# VGA.net
KiCad netlist of a schematic drawn in Altium Designer
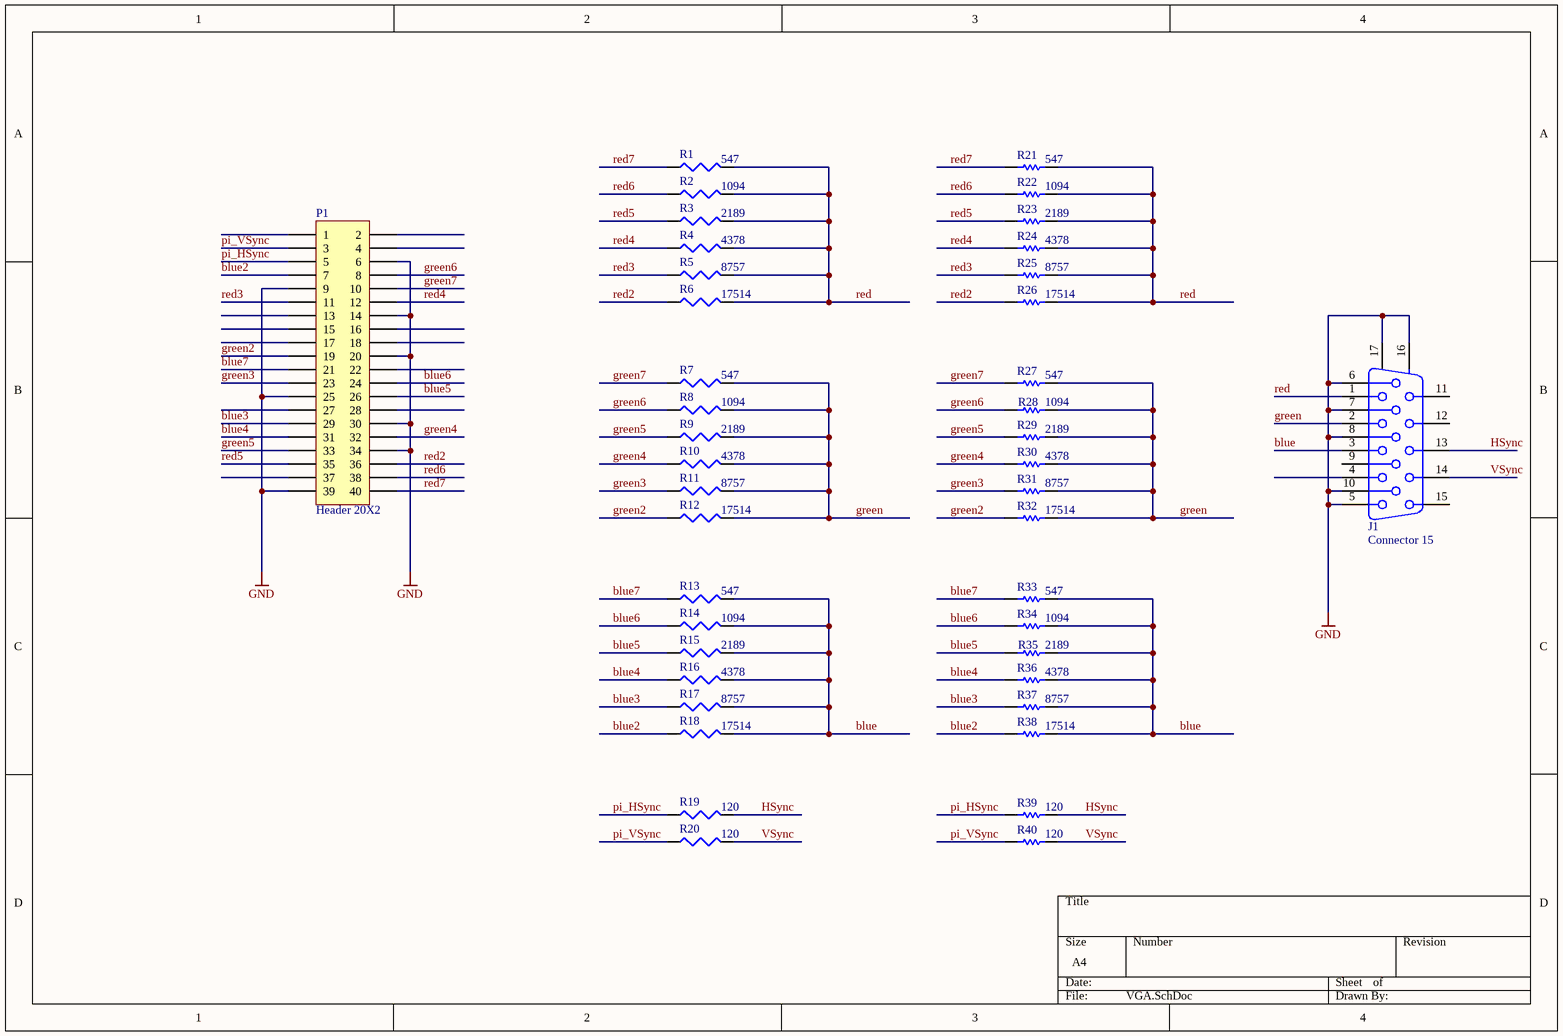
[diagram p0: VGA.SchDoc]

(export (version "E")
  (design (tool "Eeschema 10.0.6"))
  (components
    (comp (ref "J1")
      (value "Connector 15")
      (footprint "MOLEX_048203-6043")
      (description "Receptacle Assembly, 15-Pin, Sim Line Connector")
      (fields (field (name "PUBLISHER") "Altium Limited"))
      (libsource (lib "Miscellaneous Connectors") (part "Connector 15"))
    )
    (comp (ref "P1")
      (value "Header 20X2")
      (footprint "HDR2X20")
      (description "Header, 20-Pin, Dual row")
      (fields (field (name "PUBLISHER") "Altium Limited"))
      (libsource (lib "Miscellaneous Connectors") (part "Header 20X2"))
    )
    (comp (ref "R1")
      (value "547")
      (footprint "J1-0603")
      (description "Resistor")
      (fields (field (name "Comment") "Res3") (field (name "PUBLISHER") "Altium Limited"))
      (libsource (lib "Miscellaneous Devices") (part "Res3"))
    )
    (comp (ref "R2")
      (value "1094")
      (footprint "J1-0603")
      (description "Resistor")
      (fields (field (name "Comment") "Res3") (field (name "PUBLISHER") "Altium Limited"))
      (libsource (lib "Miscellaneous Devices") (part "Res3"))
    )
    (comp (ref "R3")
      (value "2189")
      (footprint "J1-0603")
      (description "Resistor")
      (fields (field (name "Comment") "Res3") (field (name "PUBLISHER") "Altium Limited"))
      (libsource (lib "Miscellaneous Devices") (part "Res3"))
    )
    (comp (ref "R4")
      (value "4378")
      (footprint "J1-0603")
      (description "Resistor")
      (fields (field (name "Comment") "Res3") (field (name "PUBLISHER") "Altium Limited"))
      (libsource (lib "Miscellaneous Devices") (part "Res3"))
    )
    (comp (ref "R5")
      (value "8757")
      (footprint "J1-0603")
      (description "Resistor")
      (fields (field (name "Comment") "Res3") (field (name "PUBLISHER") "Altium Limited"))
      (libsource (lib "Miscellaneous Devices") (part "Res3"))
    )
    (comp (ref "R6")
      (value "17514")
      (footprint "J1-0603")
      (description "Resistor")
      (fields (field (name "Comment") "Res3") (field (name "PUBLISHER") "Altium Limited"))
      (libsource (lib "Miscellaneous Devices") (part "Res3"))
    )
    (comp (ref "R7")
      (value "547")
      (footprint "J1-0603")
      (description "Resistor")
      (fields (field (name "Comment") "Res3") (field (name "PUBLISHER") "Altium Limited"))
      (libsource (lib "Miscellaneous Devices") (part "Res3"))
    )
    (comp (ref "R8")
      (value "1094")
      (footprint "J1-0603")
      (description "Resistor")
      (fields (field (name "Comment") "Res3") (field (name "PUBLISHER") "Altium Limited"))
      (libsource (lib "Miscellaneous Devices") (part "Res3"))
    )
    (comp (ref "R9")
      (value "2189")
      (footprint "J1-0603")
      (description "Resistor")
      (fields (field (name "Comment") "Res3") (field (name "PUBLISHER") "Altium Limited"))
      (libsource (lib "Miscellaneous Devices") (part "Res3"))
    )
    (comp (ref "R10")
      (value "4378")
      (footprint "J1-0603")
      (description "Resistor")
      (fields (field (name "Comment") "Res3") (field (name "PUBLISHER") "Altium Limited"))
      (libsource (lib "Miscellaneous Devices") (part "Res3"))
    )
    (comp (ref "R11")
      (value "8757")
      (footprint "J1-0603")
      (description "Resistor")
      (fields (field (name "Comment") "Res3") (field (name "PUBLISHER") "Altium Limited"))
      (libsource (lib "Miscellaneous Devices") (part "Res3"))
    )
    (comp (ref "R12")
      (value "17514")
      (footprint "J1-0603")
      (description "Resistor")
      (fields (field (name "Comment") "Res3") (field (name "PUBLISHER") "Altium Limited"))
      (libsource (lib "Miscellaneous Devices") (part "Res3"))
    )
    (comp (ref "R13")
      (value "547")
      (footprint "J1-0603")
      (description "Resistor")
      (fields (field (name "Comment") "Res3") (field (name "PUBLISHER") "Altium Limited"))
      (libsource (lib "Miscellaneous Devices") (part "Res3"))
    )
    (comp (ref "R14")
      (value "1094")
      (footprint "J1-0603")
      (description "Resistor")
      (fields (field (name "Comment") "Res3") (field (name "PUBLISHER") "Altium Limited"))
      (libsource (lib "Miscellaneous Devices") (part "Res3"))
    )
    (comp (ref "R15")
      (value "2189")
      (footprint "J1-0603")
      (description "Resistor")
      (fields (field (name "Comment") "Res3") (field (name "PUBLISHER") "Altium Limited"))
      (libsource (lib "Miscellaneous Devices") (part "Res3"))
    )
    (comp (ref "R16")
      (value "4378")
      (footprint "J1-0603")
      (description "Resistor")
      (fields (field (name "Comment") "Res3") (field (name "PUBLISHER") "Altium Limited"))
      (libsource (lib "Miscellaneous Devices") (part "Res3"))
    )
    (comp (ref "R17")
      (value "8757")
      (footprint "J1-0603")
      (description "Resistor")
      (fields (field (name "Comment") "Res3") (field (name "PUBLISHER") "Altium Limited"))
      (libsource (lib "Miscellaneous Devices") (part "Res3"))
    )
    (comp (ref "R18")
      (value "17514")
      (footprint "J1-0603")
      (description "Resistor")
      (fields (field (name "Comment") "Res3") (field (name "PUBLISHER") "Altium Limited"))
      (libsource (lib "Miscellaneous Devices") (part "Res3"))
    )
    (comp (ref "R19")
      (value "120")
      (footprint "J1-0603")
      (description "Resistor")
      (fields (field (name "Comment") "Res3") (field (name "PUBLISHER") "Altium Limited"))
      (libsource (lib "Miscellaneous Devices") (part "Res3"))
    )
    (comp (ref "R20")
      (value "120")
      (footprint "J1-0603")
      (description "Resistor")
      (fields (field (name "Comment") "Res3") (field (name "PUBLISHER") "Altium Limited"))
      (libsource (lib "Miscellaneous Devices") (part "Res3"))
    )
    (comp (ref "R21")
      (value "547")
      (footprint "AXIAL-0.3")
      (description "Resistor")
      (fields (field (name "Comment") "Res1") (field (name "PUBLISHER") "Altium Limited"))
      (libsource (lib "Miscellaneous Devices") (part "Res1"))
    )
    (comp (ref "R22")
      (value "1094")
      (footprint "AXIAL-0.3")
      (description "Resistor")
      (fields (field (name "Comment") "Res1") (field (name "PUBLISHER") "Altium Limited"))
      (libsource (lib "Miscellaneous Devices") (part "Res1"))
    )
    (comp (ref "R23")
      (value "2189")
      (footprint "AXIAL-0.3")
      (description "Resistor")
      (fields (field (name "Comment") "Res1") (field (name "PUBLISHER") "Altium Limited"))
      (libsource (lib "Miscellaneous Devices") (part "Res1"))
    )
    (comp (ref "R24")
      (value "4378")
      (footprint "AXIAL-0.3")
      (description "Resistor")
      (fields (field (name "Comment") "Res1") (field (name "PUBLISHER") "Altium Limited"))
      (libsource (lib "Miscellaneous Devices") (part "Res1"))
    )
    (comp (ref "R25")
      (value "8757")
      (footprint "AXIAL-0.3")
      (description "Resistor")
      (fields (field (name "Comment") "Res1") (field (name "PUBLISHER") "Altium Limited"))
      (libsource (lib "Miscellaneous Devices") (part "Res1"))
    )
    (comp (ref "R26")
      (value "17514")
      (footprint "AXIAL-0.3")
      (description "Resistor")
      (fields (field (name "Comment") "Res1") (field (name "PUBLISHER") "Altium Limited"))
      (libsource (lib "Miscellaneous Devices") (part "Res1"))
    )
    (comp (ref "R27")
      (value "547")
      (footprint "AXIAL-0.3")
      (description "Resistor")
      (fields (field (name "Comment") "Res1") (field (name "PUBLISHER") "Altium Limited"))
      (libsource (lib "Miscellaneous Devices") (part "Res1"))
    )
    (comp (ref "R28")
      (value "1094")
      (footprint "AXIAL-0.3")
      (description "Resistor")
      (fields (field (name "Comment") "Res1") (field (name "PUBLISHER") "Altium Limited"))
      (libsource (lib "Miscellaneous Devices") (part "Res1"))
    )
    (comp (ref "R29")
      (value "2189")
      (footprint "AXIAL-0.3")
      (description "Resistor")
      (fields (field (name "Comment") "Res1") (field (name "PUBLISHER") "Altium Limited"))
      (libsource (lib "Miscellaneous Devices") (part "Res1"))
    )
    (comp (ref "R30")
      (value "4378")
      (footprint "AXIAL-0.3")
      (description "Resistor")
      (fields (field (name "Comment") "Res1") (field (name "PUBLISHER") "Altium Limited"))
      (libsource (lib "Miscellaneous Devices") (part "Res1"))
    )
    (comp (ref "R31")
      (value "8757")
      (footprint "AXIAL-0.3")
      (description "Resistor")
      (fields (field (name "Comment") "Res1") (field (name "PUBLISHER") "Altium Limited"))
      (libsource (lib "Miscellaneous Devices") (part "Res1"))
    )
    (comp (ref "R32")
      (value "17514")
      (footprint "AXIAL-0.3")
      (description "Resistor")
      (fields (field (name "Comment") "Res1") (field (name "PUBLISHER") "Altium Limited"))
      (libsource (lib "Miscellaneous Devices") (part "Res1"))
    )
    (comp (ref "R33")
      (value "547")
      (footprint "AXIAL-0.3")
      (description "Resistor")
      (fields (field (name "Comment") "Res1") (field (name "PUBLISHER") "Altium Limited"))
      (libsource (lib "Miscellaneous Devices") (part "Res1"))
    )
    (comp (ref "R34")
      (value "1094")
      (footprint "AXIAL-0.3")
      (description "Resistor")
      (fields (field (name "Comment") "Res1") (field (name "PUBLISHER") "Altium Limited"))
      (libsource (lib "Miscellaneous Devices") (part "Res1"))
    )
    (comp (ref "R35")
      (value "2189")
      (footprint "AXIAL-0.3")
      (description "Resistor")
      (fields (field (name "Comment") "Res1") (field (name "PUBLISHER") "Altium Limited"))
      (libsource (lib "Miscellaneous Devices") (part "Res1"))
    )
    (comp (ref "R36")
      (value "4378")
      (footprint "AXIAL-0.3")
      (description "Resistor")
      (fields (field (name "Comment") "Res1") (field (name "PUBLISHER") "Altium Limited"))
      (libsource (lib "Miscellaneous Devices") (part "Res1"))
    )
    (comp (ref "R37")
      (value "8757")
      (footprint "AXIAL-0.3")
      (description "Resistor")
      (fields (field (name "Comment") "Res1") (field (name "PUBLISHER") "Altium Limited"))
      (libsource (lib "Miscellaneous Devices") (part "Res1"))
    )
    (comp (ref "R38")
      (value "17514")
      (footprint "AXIAL-0.3")
      (description "Resistor")
      (fields (field (name "Comment") "Res1") (field (name "PUBLISHER") "Altium Limited"))
      (libsource (lib "Miscellaneous Devices") (part "Res1"))
    )
    (comp (ref "R39")
      (value "120")
      (footprint "AXIAL-0.3")
      (description "Resistor")
      (fields (field (name "Comment") "Res1") (field (name "PUBLISHER") "Altium Limited"))
      (libsource (lib "Miscellaneous Devices") (part "Res1"))
    )
    (comp (ref "R40")
      (value "120")
      (footprint "AXIAL-0.3")
      (description "Resistor")
      (fields (field (name "Comment") "Res1") (field (name "PUBLISHER") "Altium Limited"))
      (libsource (lib "Miscellaneous Devices") (part "Res1"))
    )
  )
  (nets
    (net (code "1") (name "/HSync") (class "Default")
      (node (ref "J1") (pin "13") (pinfunction "13_13") (pintype "passive"))
      (node (ref "R19") (pin "2") (pinfunction "2_2") (pintype "passive"))
      (node (ref "R39") (pin "2") (pinfunction "2_2") (pintype "passive"))
    )
    (net (code "2") (name "/VSync") (class "Default")
      (node (ref "J1") (pin "14") (pinfunction "14_14") (pintype "passive"))
      (node (ref "R20") (pin "2") (pinfunction "2_2") (pintype "passive"))
      (node (ref "R40") (pin "2") (pinfunction "2_2") (pintype "passive"))
    )
    (net (code "3") (name "/blue") (class "Default")
      (node (ref "J1") (pin "3") (pinfunction "3_3") (pintype "passive"))
      (node (ref "R13") (pin "2") (pinfunction "2_2") (pintype "passive"))
      (node (ref "R14") (pin "2") (pinfunction "2_2") (pintype "passive"))
      (node (ref "R15") (pin "2") (pinfunction "2_2") (pintype "passive"))
      (node (ref "R16") (pin "2") (pinfunction "2_2") (pintype "passive"))
      (node (ref "R17") (pin "2") (pinfunction "2_2") (pintype "passive"))
      (node (ref "R18") (pin "2") (pinfunction "2_2") (pintype "passive"))
      (node (ref "R33") (pin "2") (pinfunction "2_2") (pintype "passive"))
      (node (ref "R34") (pin "2") (pinfunction "2_2") (pintype "passive"))
      (node (ref "R35") (pin "2") (pinfunction "2_2") (pintype "passive"))
      (node (ref "R36") (pin "2") (pinfunction "2_2") (pintype "passive"))
      (node (ref "R37") (pin "2") (pinfunction "2_2") (pintype "passive"))
      (node (ref "R38") (pin "2") (pinfunction "2_2") (pintype "passive"))
    )
    (net (code "4") (name "/blue2") (class "Default")
      (node (ref "P1") (pin "7") (pinfunction "7_7") (pintype "passive"))
      (node (ref "R18") (pin "1") (pinfunction "1_1") (pintype "passive"))
      (node (ref "R38") (pin "1") (pinfunction "1_1") (pintype "passive"))
    )
    (net (code "5") (name "/blue3") (class "Default")
      (node (ref "P1") (pin "29") (pinfunction "29_29") (pintype "passive"))
      (node (ref "R17") (pin "1") (pinfunction "1_1") (pintype "passive"))
      (node (ref "R37") (pin "1") (pinfunction "1_1") (pintype "passive"))
    )
    (net (code "6") (name "/blue4") (class "Default")
      (node (ref "P1") (pin "31") (pinfunction "31_31") (pintype "passive"))
      (node (ref "R16") (pin "1") (pinfunction "1_1") (pintype "passive"))
      (node (ref "R36") (pin "1") (pinfunction "1_1") (pintype "passive"))
    )
    (net (code "7") (name "/blue5") (class "Default")
      (node (ref "P1") (pin "26") (pinfunction "26_26") (pintype "passive"))
      (node (ref "R15") (pin "1") (pinfunction "1_1") (pintype "passive"))
      (node (ref "R35") (pin "1") (pinfunction "1_1") (pintype "passive"))
    )
    (net (code "8") (name "/blue6") (class "Default")
      (node (ref "P1") (pin "24") (pinfunction "24_24") (pintype "passive"))
      (node (ref "R14") (pin "1") (pinfunction "1_1") (pintype "passive"))
      (node (ref "R34") (pin "1") (pinfunction "1_1") (pintype "passive"))
    )
    (net (code "9") (name "/blue7") (class "Default")
      (node (ref "P1") (pin "21") (pinfunction "21_21") (pintype "passive"))
      (node (ref "R13") (pin "1") (pinfunction "1_1") (pintype "passive"))
      (node (ref "R33") (pin "1") (pinfunction "1_1") (pintype "passive"))
    )
    (net (code "10") (name "/green") (class "Default")
      (node (ref "J1") (pin "2") (pinfunction "2_2") (pintype "passive"))
      (node (ref "R10") (pin "2") (pinfunction "2_2") (pintype "passive"))
      (node (ref "R11") (pin "2") (pinfunction "2_2") (pintype "passive"))
      (node (ref "R12") (pin "2") (pinfunction "2_2") (pintype "passive"))
      (node (ref "R27") (pin "2") (pinfunction "2_2") (pintype "passive"))
      (node (ref "R28") (pin "2") (pinfunction "2_2") (pintype "passive"))
      (node (ref "R29") (pin "2") (pinfunction "2_2") (pintype "passive"))
      (node (ref "R30") (pin "2") (pinfunction "2_2") (pintype "passive"))
      (node (ref "R31") (pin "2") (pinfunction "2_2") (pintype "passive"))
      (node (ref "R32") (pin "2") (pinfunction "2_2") (pintype "passive"))
      (node (ref "R7") (pin "2") (pinfunction "2_2") (pintype "passive"))
      (node (ref "R8") (pin "2") (pinfunction "2_2") (pintype "passive"))
      (node (ref "R9") (pin "2") (pinfunction "2_2") (pintype "passive"))
    )
    (net (code "11") (name "/green2") (class "Default")
      (node (ref "P1") (pin "19") (pinfunction "19_19") (pintype "passive"))
      (node (ref "R12") (pin "1") (pinfunction "1_1") (pintype "passive"))
      (node (ref "R32") (pin "1") (pinfunction "1_1") (pintype "passive"))
    )
    (net (code "12") (name "/green3") (class "Default")
      (node (ref "P1") (pin "23") (pinfunction "23_23") (pintype "passive"))
      (node (ref "R11") (pin "1") (pinfunction "1_1") (pintype "passive"))
      (node (ref "R31") (pin "1") (pinfunction "1_1") (pintype "passive"))
    )
    (net (code "13") (name "/green4") (class "Default")
      (node (ref "P1") (pin "32") (pinfunction "32_32") (pintype "passive"))
      (node (ref "R10") (pin "1") (pinfunction "1_1") (pintype "passive"))
      (node (ref "R30") (pin "1") (pinfunction "1_1") (pintype "passive"))
    )
    (net (code "14") (name "/green5") (class "Default")
      (node (ref "P1") (pin "33") (pinfunction "33_33") (pintype "passive"))
      (node (ref "R29") (pin "1") (pinfunction "1_1") (pintype "passive"))
      (node (ref "R9") (pin "1") (pinfunction "1_1") (pintype "passive"))
    )
    (net (code "15") (name "/green6") (class "Default")
      (node (ref "P1") (pin "8") (pinfunction "8_8") (pintype "passive"))
      (node (ref "R28") (pin "1") (pinfunction "1_1") (pintype "passive"))
      (node (ref "R8") (pin "1") (pinfunction "1_1") (pintype "passive"))
    )
    (net (code "16") (name "/green7") (class "Default")
      (node (ref "P1") (pin "10") (pinfunction "10_10") (pintype "passive"))
      (node (ref "R27") (pin "1") (pinfunction "1_1") (pintype "passive"))
      (node (ref "R7") (pin "1") (pinfunction "1_1") (pintype "passive"))
    )
    (net (code "17") (name "/pi_HSync") (class "Default")
      (node (ref "P1") (pin "5") (pinfunction "5_5") (pintype "passive"))
      (node (ref "R19") (pin "1") (pinfunction "1_1") (pintype "passive"))
      (node (ref "R39") (pin "1") (pinfunction "1_1") (pintype "passive"))
    )
    (net (code "18") (name "/pi_VSync") (class "Default")
      (node (ref "P1") (pin "3") (pinfunction "3_3") (pintype "passive"))
      (node (ref "R20") (pin "1") (pinfunction "1_1") (pintype "passive"))
      (node (ref "R40") (pin "1") (pinfunction "1_1") (pintype "passive"))
    )
    (net (code "19") (name "/red") (class "Default")
      (node (ref "J1") (pin "1") (pinfunction "1_1") (pintype "passive"))
      (node (ref "R1") (pin "2") (pinfunction "2_2") (pintype "passive"))
      (node (ref "R2") (pin "2") (pinfunction "2_2") (pintype "passive"))
      (node (ref "R21") (pin "2") (pinfunction "2_2") (pintype "passive"))
      (node (ref "R22") (pin "2") (pinfunction "2_2") (pintype "passive"))
      (node (ref "R23") (pin "2") (pinfunction "2_2") (pintype "passive"))
      (node (ref "R24") (pin "2") (pinfunction "2_2") (pintype "passive"))
      (node (ref "R25") (pin "2") (pinfunction "2_2") (pintype "passive"))
      (node (ref "R26") (pin "2") (pinfunction "2_2") (pintype "passive"))
      (node (ref "R3") (pin "2") (pinfunction "2_2") (pintype "passive"))
      (node (ref "R4") (pin "2") (pinfunction "2_2") (pintype "passive"))
      (node (ref "R5") (pin "2") (pinfunction "2_2") (pintype "passive"))
      (node (ref "R6") (pin "2") (pinfunction "2_2") (pintype "passive"))
    )
    (net (code "20") (name "/red2") (class "Default")
      (node (ref "P1") (pin "36") (pinfunction "36_36") (pintype "passive"))
      (node (ref "R26") (pin "1") (pinfunction "1_1") (pintype "passive"))
      (node (ref "R6") (pin "1") (pinfunction "1_1") (pintype "passive"))
    )
    (net (code "21") (name "/red3") (class "Default")
      (node (ref "P1") (pin "11") (pinfunction "11_11") (pintype "passive"))
      (node (ref "R25") (pin "1") (pinfunction "1_1") (pintype "passive"))
      (node (ref "R5") (pin "1") (pinfunction "1_1") (pintype "passive"))
    )
    (net (code "22") (name "/red4") (class "Default")
      (node (ref "P1") (pin "12") (pinfunction "12_12") (pintype "passive"))
      (node (ref "R24") (pin "1") (pinfunction "1_1") (pintype "passive"))
      (node (ref "R4") (pin "1") (pinfunction "1_1") (pintype "passive"))
    )
    (net (code "23") (name "/red5") (class "Default")
      (node (ref "P1") (pin "35") (pinfunction "35_35") (pintype "passive"))
      (node (ref "R23") (pin "1") (pinfunction "1_1") (pintype "passive"))
      (node (ref "R3") (pin "1") (pinfunction "1_1") (pintype "passive"))
    )
    (net (code "24") (name "/red6") (class "Default")
      (node (ref "P1") (pin "38") (pinfunction "38_38") (pintype "passive"))
      (node (ref "R2") (pin "1") (pinfunction "1_1") (pintype "passive"))
      (node (ref "R22") (pin "1") (pinfunction "1_1") (pintype "passive"))
    )
    (net (code "25") (name "/red7") (class "Default")
      (node (ref "P1") (pin "40") (pinfunction "40_40") (pintype "passive"))
      (node (ref "R1") (pin "1") (pinfunction "1_1") (pintype "passive"))
      (node (ref "R21") (pin "1") (pinfunction "1_1") (pintype "passive"))
    )
    (net (code "26") (name "GND") (class "Default")
      (node (ref "J1") (pin "10") (pinfunction "10_10") (pintype "passive"))
      (node (ref "J1") (pin "16") (pinfunction "MH1_16") (pintype "passive"))
      (node (ref "J1") (pin "17") (pinfunction "MH2_17") (pintype "passive"))
      (node (ref "J1") (pin "5") (pinfunction "5_5") (pintype "passive"))
      (node (ref "J1") (pin "6") (pinfunction "6_6") (pintype "passive"))
      (node (ref "J1") (pin "7") (pinfunction "7_7") (pintype "passive"))
      (node (ref "J1") (pin "8") (pinfunction "8_8") (pintype "passive"))
      (node (ref "P1") (pin "14") (pinfunction "14_14") (pintype "passive"))
      (node (ref "P1") (pin "20") (pinfunction "20_20") (pintype "passive"))
      (node (ref "P1") (pin "25") (pinfunction "25_25") (pintype "passive"))
      (node (ref "P1") (pin "30") (pinfunction "30_30") (pintype "passive"))
      (node (ref "P1") (pin "34") (pinfunction "34_34") (pintype "passive"))
      (node (ref "P1") (pin "39") (pinfunction "39_39") (pintype "passive"))
      (node (ref "P1") (pin "6") (pinfunction "6_6") (pintype "passive"))
      (node (ref "P1") (pin "9") (pinfunction "9_9") (pintype "passive"))
    )
    (net (code "27") (name "unconnected-(J1-Pad4)") (class "Default")
      (node (ref "J1") (pin "4") (pinfunction "4_4") (pintype "passive"))
    )
    (net (code "28") (name "unconnected-(J1-Pad9)") (class "Default")
      (node (ref "J1") (pin "9") (pinfunction "9_9") (pintype "passive"))
    )
    (net (code "29") (name "unconnected-(J1-Pad11)") (class "Default")
      (node (ref "J1") (pin "11") (pinfunction "11_11") (pintype "passive"))
    )
    (net (code "30") (name "unconnected-(J1-Pad12)") (class "Default")
      (node (ref "J1") (pin "12") (pinfunction "12_12") (pintype "passive"))
    )
    (net (code "31") (name "unconnected-(J1-Pad15)") (class "Default")
      (node (ref "J1") (pin "15") (pinfunction "15_15") (pintype "passive"))
    )
    (net (code "32") (name "unconnected-(P1-Pad1)") (class "Default")
      (node (ref "P1") (pin "1") (pinfunction "1_1") (pintype "passive"))
    )
    (net (code "33") (name "unconnected-(P1-Pad2)") (class "Default")
      (node (ref "P1") (pin "2") (pinfunction "2_2") (pintype "passive"))
    )
    (net (code "34") (name "unconnected-(P1-Pad4)") (class "Default")
      (node (ref "P1") (pin "4") (pinfunction "4_4") (pintype "passive"))
    )
    (net (code "35") (name "unconnected-(P1-Pad13)") (class "Default")
      (node (ref "P1") (pin "13") (pinfunction "13_13") (pintype "passive"))
    )
    (net (code "36") (name "unconnected-(P1-Pad15)") (class "Default")
      (node (ref "P1") (pin "15") (pinfunction "15_15") (pintype "passive"))
    )
    (net (code "37") (name "unconnected-(P1-Pad16)") (class "Default")
      (node (ref "P1") (pin "16") (pinfunction "16_16") (pintype "passive"))
    )
    (net (code "38") (name "unconnected-(P1-Pad17)") (class "Default")
      (node (ref "P1") (pin "17") (pinfunction "17_17") (pintype "passive"))
    )
    (net (code "39") (name "unconnected-(P1-Pad18)") (class "Default")
      (node (ref "P1") (pin "18") (pinfunction "18_18") (pintype "passive"))
    )
    (net (code "40") (name "unconnected-(P1-Pad22)") (class "Default")
      (node (ref "P1") (pin "22") (pinfunction "22_22") (pintype "passive"))
    )
    (net (code "41") (name "unconnected-(P1-Pad27)") (class "Default")
      (node (ref "P1") (pin "27") (pinfunction "27_27") (pintype "passive"))
    )
    (net (code "42") (name "unconnected-(P1-Pad28)") (class "Default")
      (node (ref "P1") (pin "28") (pinfunction "28_28") (pintype "passive"))
    )
    (net (code "43") (name "unconnected-(P1-Pad37)") (class "Default")
      (node (ref "P1") (pin "37") (pinfunction "37_37") (pintype "passive"))
    )
  )
)
